# Schematic_monitoring.net
KiCad netlist of a schematic drawn in EasyEDA
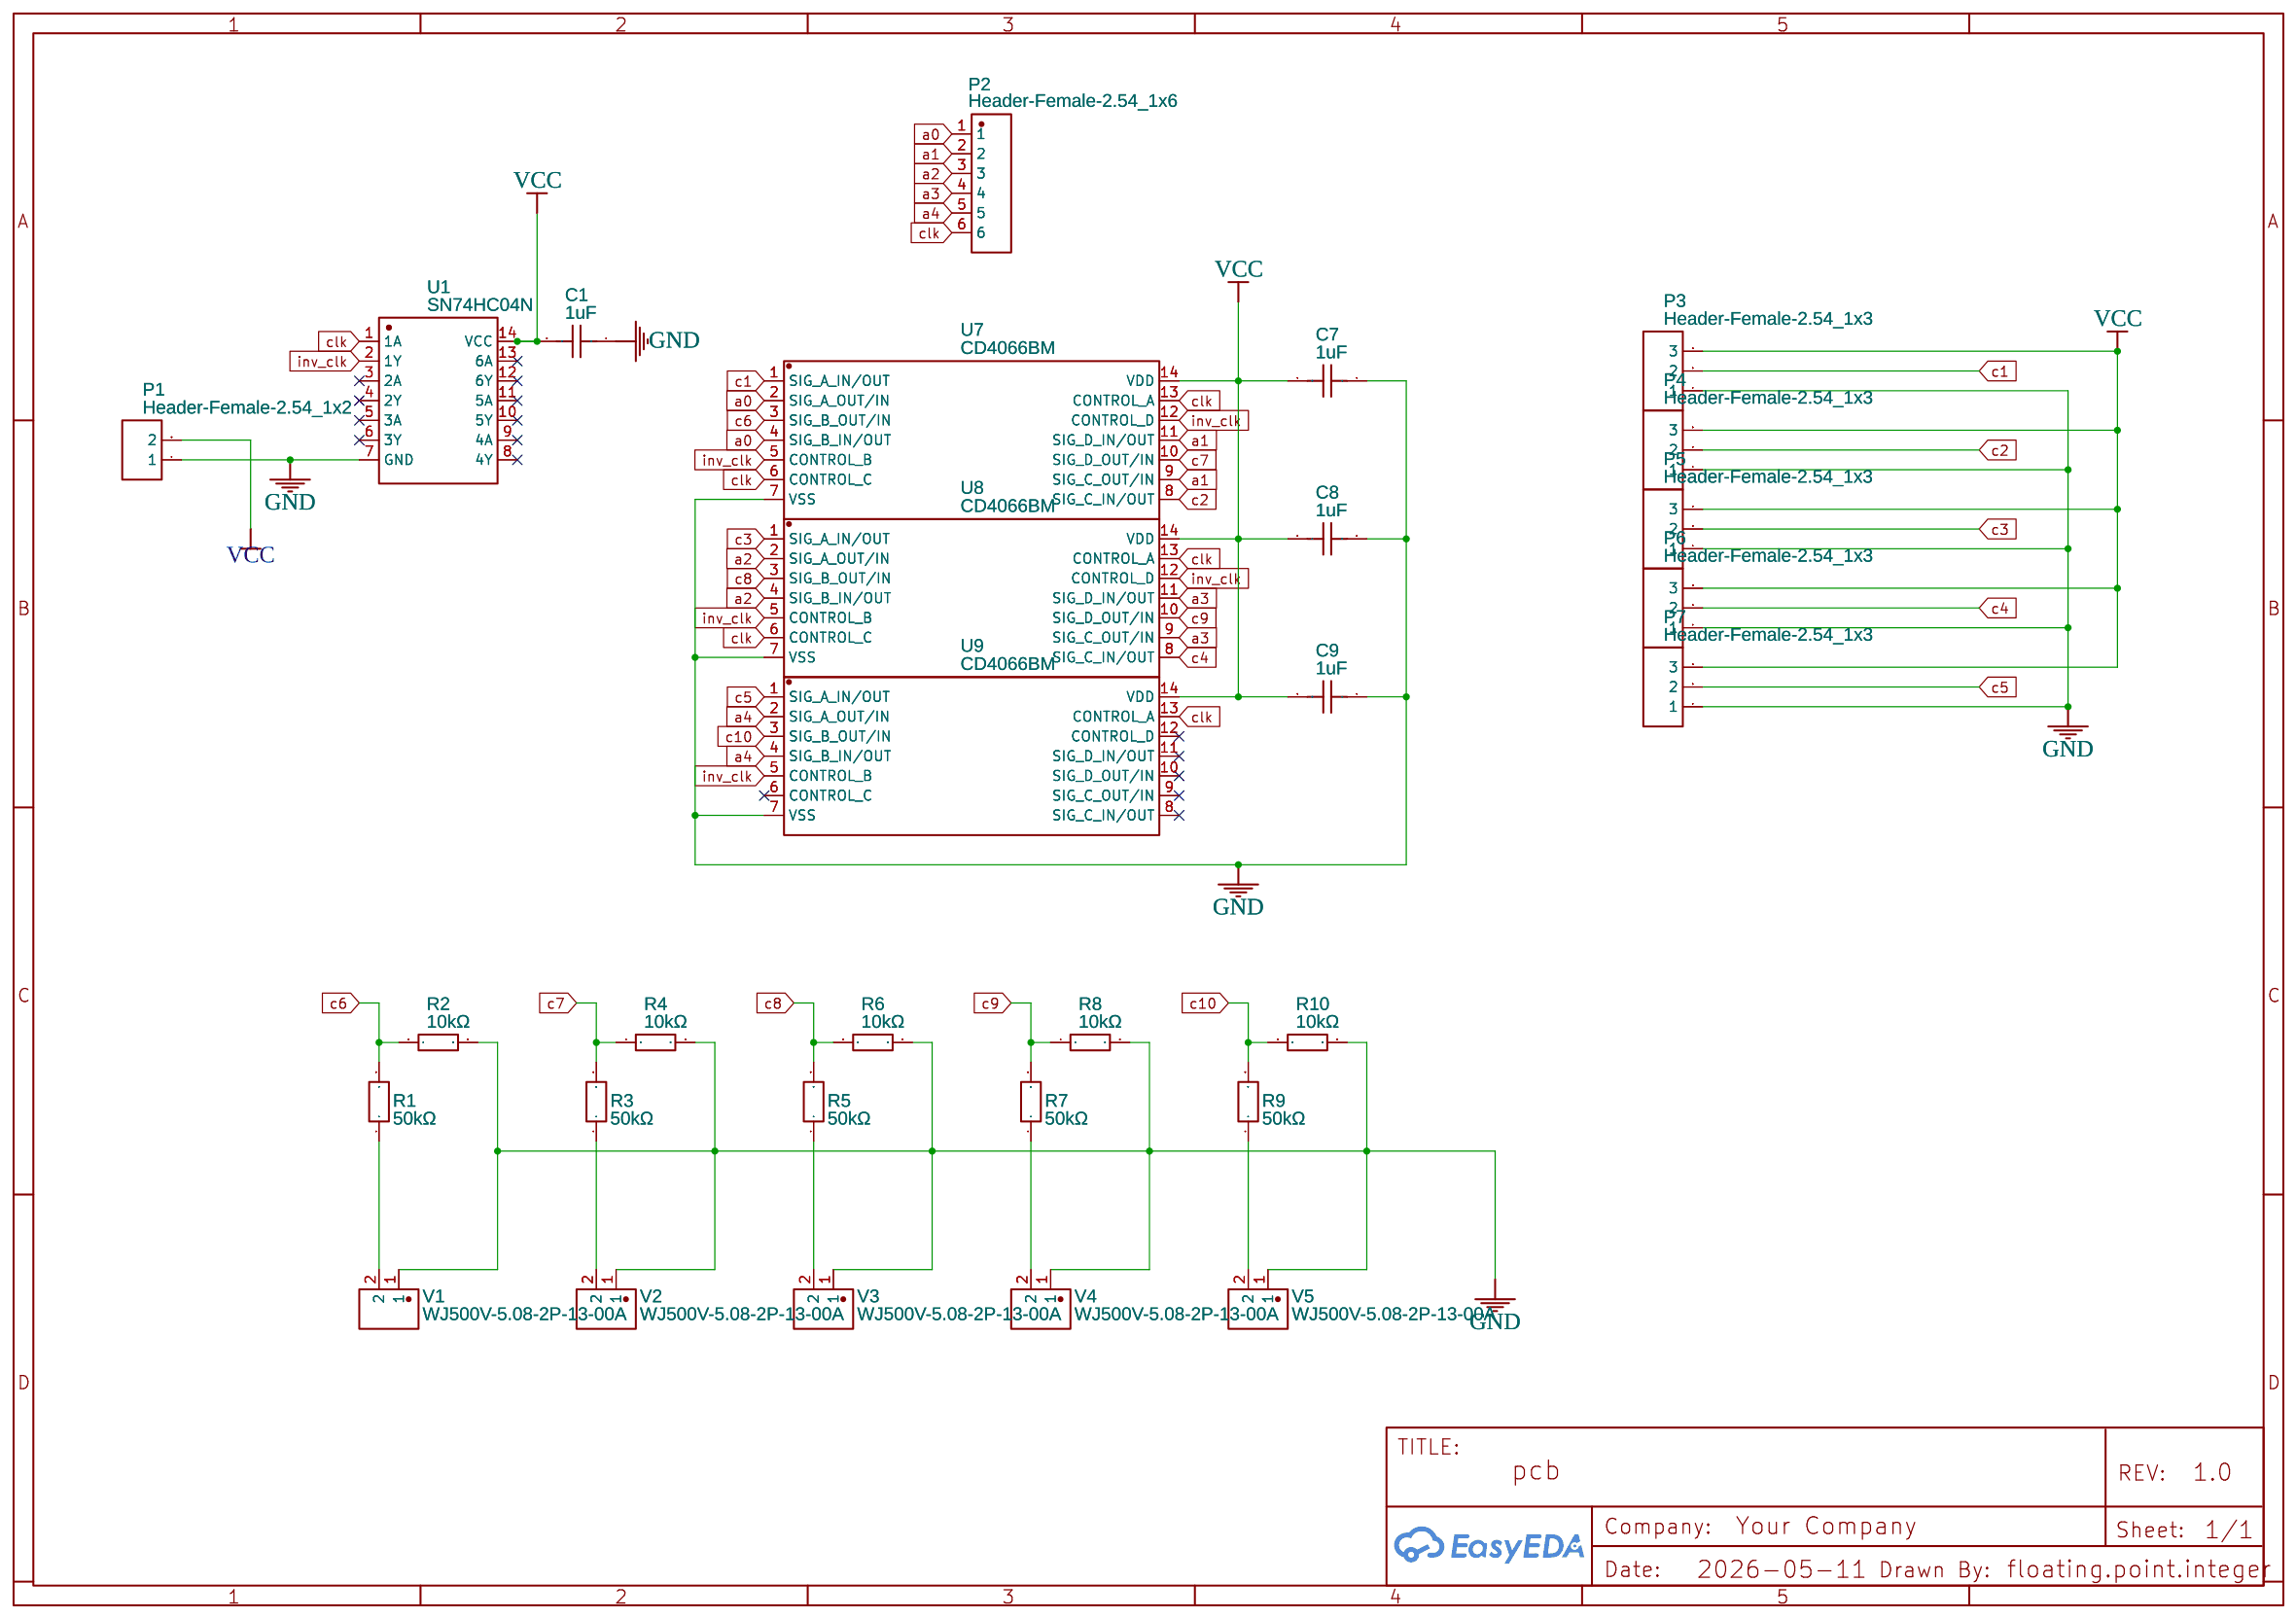
[diagram p0: schematic sheet]

(export (version "E")
  (design (tool "Eeschema 10.0.6"))
  (components
    (comp (ref "C1")
      (value "1uF")
      (fields (field (name "Manufacturer Part") "0603B105K250CT") (field (name "Manufacturer") "Walsin(华新科)"))
      (libsource (lib "") (part "0603B105K250CT"))
    )
    (comp (ref "C7")
      (value "1uF")
      (fields (field (name "Manufacturer Part") "0603B105K250CT") (field (name "Manufacturer") "Walsin(华新科)"))
      (libsource (lib "") (part "0603B105K250CT"))
    )
    (comp (ref "C8")
      (value "1uF")
      (fields (field (name "Manufacturer Part") "0603B105K250CT") (field (name "Manufacturer") "Walsin(华新科)"))
      (libsource (lib "") (part "0603B105K250CT"))
    )
    (comp (ref "C9")
      (value "1uF")
      (fields (field (name "Manufacturer Part") "0603B105K250CT") (field (name "Manufacturer") "Walsin(华新科)"))
      (libsource (lib "") (part "0603B105K250CT"))
    )
    (comp (ref "P1")
      (value "Header-Female-2.54_1x2")
      (fields (field (name "Manufacturer Part") "2.54-1*2P母") (field (name "Manufacturer") "BOOMELE(博穆精密)"))
      (libsource (lib "") (part "Header-Female-2.54_1x2"))
    )
    (comp (ref "P2")
      (value "Header-Female-2.54_1x6")
      (fields (field (name "Manufacturer Part") "2.54-1*6P母") (field (name "Manufacturer") "BOOMELE(博穆精密)"))
      (libsource (lib "") (part "Header-Female-2.54_1x6"))
    )
    (comp (ref "P3")
      (value "Header-Female-2.54_1x3")
      (fields (field (name "Manufacturer Part") "2.54-1*3P母") (field (name "Manufacturer") "BOOMELE(博穆精密)"))
      (libsource (lib "") (part "Header-Female-2.54_1x3"))
    )
    (comp (ref "P4")
      (value "Header-Female-2.54_1x3")
      (fields (field (name "Manufacturer Part") "2.54-1*3P母") (field (name "Manufacturer") "BOOMELE(博穆精密)"))
      (libsource (lib "") (part "Header-Female-2.54_1x3"))
    )
    (comp (ref "P5")
      (value "Header-Female-2.54_1x3")
      (fields (field (name "Manufacturer Part") "2.54-1*3P母") (field (name "Manufacturer") "BOOMELE(博穆精密)"))
      (libsource (lib "") (part "Header-Female-2.54_1x3"))
    )
    (comp (ref "P6")
      (value "Header-Female-2.54_1x3")
      (fields (field (name "Manufacturer Part") "2.54-1*3P母") (field (name "Manufacturer") "BOOMELE(博穆精密)"))
      (libsource (lib "") (part "Header-Female-2.54_1x3"))
    )
    (comp (ref "P7")
      (value "Header-Female-2.54_1x3")
      (fields (field (name "Manufacturer Part") "2.54-1*3P母") (field (name "Manufacturer") "BOOMELE(博穆精密)"))
      (libsource (lib "") (part "Header-Female-2.54_1x3"))
    )
    (comp (ref "R1")
      (value "50kΩ")
      (fields (field (name "Manufacturer Part") "RT0603BRD0750KL") (field (name "Manufacturer") "YAGEO(国巨)"))
      (libsource (lib "") (part "RT0603BRD0750KL"))
    )
    (comp (ref "R2")
      (value "10kΩ")
      (fields (field (name "Manufacturer Part") "RT0603DRD0710KL") (field (name "Manufacturer") "YAGEO(国巨)"))
      (libsource (lib "") (part "RT0603DRD0710KL"))
    )
    (comp (ref "R3")
      (value "50kΩ")
      (fields (field (name "Manufacturer Part") "RT0603BRD0750KL") (field (name "Manufacturer") "YAGEO(国巨)"))
      (libsource (lib "") (part "RT0603BRD0750KL"))
    )
    (comp (ref "R4")
      (value "10kΩ")
      (fields (field (name "Manufacturer Part") "RT0603DRD0710KL") (field (name "Manufacturer") "YAGEO(国巨)"))
      (libsource (lib "") (part "RT0603DRD0710KL"))
    )
    (comp (ref "R5")
      (value "50kΩ")
      (fields (field (name "Manufacturer Part") "RT0603BRD0750KL") (field (name "Manufacturer") "YAGEO(国巨)"))
      (libsource (lib "") (part "RT0603BRD0750KL"))
    )
    (comp (ref "R6")
      (value "10kΩ")
      (fields (field (name "Manufacturer Part") "RT0603DRD0710KL") (field (name "Manufacturer") "YAGEO(国巨)"))
      (libsource (lib "") (part "RT0603DRD0710KL"))
    )
    (comp (ref "R7")
      (value "50kΩ")
      (fields (field (name "Manufacturer Part") "RT0603BRD0750KL") (field (name "Manufacturer") "YAGEO(国巨)"))
      (libsource (lib "") (part "RT0603BRD0750KL"))
    )
    (comp (ref "R8")
      (value "10kΩ")
      (fields (field (name "Manufacturer Part") "RT0603DRD0710KL") (field (name "Manufacturer") "YAGEO(国巨)"))
      (libsource (lib "") (part "RT0603DRD0710KL"))
    )
    (comp (ref "R9")
      (value "50kΩ")
      (fields (field (name "Manufacturer Part") "RT0603BRD0750KL") (field (name "Manufacturer") "YAGEO(国巨)"))
      (libsource (lib "") (part "RT0603BRD0750KL"))
    )
    (comp (ref "R10")
      (value "10kΩ")
      (fields (field (name "Manufacturer Part") "RT0603DRD0710KL") (field (name "Manufacturer") "YAGEO(国巨)"))
      (libsource (lib "") (part "RT0603DRD0710KL"))
    )
    (comp (ref "U1")
      (value "SN74HC04N")
      (fields (field (name "Manufacturer") "TI(德州仪器)"))
      (libsource (lib "") (part "SN74HC04N"))
    )
    (comp (ref "U7")
      (value "CD4066BM")
      (fields (field (name "Manufacturer") "TI(德州仪器)"))
      (libsource (lib "") (part "CD4066BM"))
    )
    (comp (ref "U8")
      (value "CD4066BM")
      (fields (field (name "Manufacturer") "TI(德州仪器)"))
      (libsource (lib "") (part "CD4066BM"))
    )
    (comp (ref "U9")
      (value "CD4066BM")
      (fields (field (name "Manufacturer") "TI(德州仪器)"))
      (libsource (lib "") (part "CD4066BM"))
    )
    (comp (ref "V1")
      (value "WJ500V-5.08-2P-13-00A")
      (fields
        (field (name "Manufacturer Part") "WJ500V-5.08-02P-13-00A")
        (field (name "Manufacturer") "KANGNEX(康奈克斯电气)")
      )
      (libsource (lib "") (part "WJ500V-5.08-2P-13-00A"))
    )
    (comp (ref "V2")
      (value "WJ500V-5.08-2P-13-00A")
      (fields
        (field (name "Manufacturer Part") "WJ500V-5.08-02P-13-00A")
        (field (name "Manufacturer") "KANGNEX(康奈克斯电气)")
      )
      (libsource (lib "") (part "WJ500V-5.08-2P-13-00A"))
    )
    (comp (ref "V3")
      (value "WJ500V-5.08-2P-13-00A")
      (fields
        (field (name "Manufacturer Part") "WJ500V-5.08-02P-13-00A")
        (field (name "Manufacturer") "KANGNEX(康奈克斯电气)")
      )
      (libsource (lib "") (part "WJ500V-5.08-2P-13-00A"))
    )
    (comp (ref "V4")
      (value "WJ500V-5.08-2P-13-00A")
      (fields
        (field (name "Manufacturer Part") "WJ500V-5.08-02P-13-00A")
        (field (name "Manufacturer") "KANGNEX(康奈克斯电气)")
      )
      (libsource (lib "") (part "WJ500V-5.08-2P-13-00A"))
    )
    (comp (ref "V5")
      (value "WJ500V-5.08-2P-13-00A")
      (fields
        (field (name "Manufacturer Part") "WJ500V-5.08-02P-13-00A")
        (field (name "Manufacturer") "KANGNEX(康奈克斯电气)")
      )
      (libsource (lib "") (part "WJ500V-5.08-2P-13-00A"))
    )
  )
  (nets
    (net (code "1") (name "GND") (class "Default")
      (node (ref "C1") (pin "1") (pinfunction "1_1") (pintype "unspecified"))
      (node (ref "C7") (pin "1") (pinfunction "1_1") (pintype "unspecified"))
      (node (ref "C8") (pin "1") (pinfunction "1_1") (pintype "unspecified"))
      (node (ref "C9") (pin "1") (pinfunction "1_1") (pintype "unspecified"))
      (node (ref "P1") (pin "1") (pinfunction "1_1") (pintype "input"))
      (node (ref "P3") (pin "1") (pinfunction "1_1") (pintype "input"))
      (node (ref "P4") (pin "1") (pinfunction "1_1") (pintype "input"))
      (node (ref "P5") (pin "1") (pinfunction "1_1") (pintype "input"))
      (node (ref "P6") (pin "1") (pinfunction "1_1") (pintype "input"))
      (node (ref "P7") (pin "1") (pinfunction "1_1") (pintype "input"))
      (node (ref "R10") (pin "2") (pinfunction "2_2") (pintype "unspecified"))
      (node (ref "R2") (pin "2") (pinfunction "2_2") (pintype "unspecified"))
      (node (ref "R4") (pin "2") (pinfunction "2_2") (pintype "unspecified"))
      (node (ref "R6") (pin "2") (pinfunction "2_2") (pintype "unspecified"))
      (node (ref "R8") (pin "2") (pinfunction "2_2") (pintype "unspecified"))
      (node (ref "U1") (pin "7") (pinfunction "GND_7") (pintype "unspecified"))
      (node (ref "U7") (pin "7") (pinfunction "VSS_7") (pintype "unspecified"))
      (node (ref "U8") (pin "7") (pinfunction "VSS_7") (pintype "unspecified"))
      (node (ref "U9") (pin "7") (pinfunction "VSS_7") (pintype "unspecified"))
      (node (ref "V1") (pin "1") (pinfunction "1_1") (pintype "unspecified"))
      (node (ref "V2") (pin "1") (pinfunction "1_1") (pintype "unspecified"))
      (node (ref "V3") (pin "1") (pinfunction "1_1") (pintype "unspecified"))
      (node (ref "V4") (pin "1") (pinfunction "1_1") (pintype "unspecified"))
      (node (ref "V5") (pin "1") (pinfunction "1_1") (pintype "unspecified"))
    )
    (net (code "2") (name "Net-(R1-Pad1)") (class "Default")
      (node (ref "R1") (pin "1") (pinfunction "1_1") (pintype "unspecified"))
      (node (ref "V1") (pin "2") (pinfunction "2_2") (pintype "unspecified"))
    )
    (net (code "3") (name "Net-(R3-Pad1)") (class "Default")
      (node (ref "R3") (pin "1") (pinfunction "1_1") (pintype "unspecified"))
      (node (ref "V2") (pin "2") (pinfunction "2_2") (pintype "unspecified"))
    )
    (net (code "4") (name "Net-(R5-Pad1)") (class "Default")
      (node (ref "R5") (pin "1") (pinfunction "1_1") (pintype "unspecified"))
      (node (ref "V3") (pin "2") (pinfunction "2_2") (pintype "unspecified"))
    )
    (net (code "5") (name "Net-(R7-Pad1)") (class "Default")
      (node (ref "R7") (pin "1") (pinfunction "1_1") (pintype "unspecified"))
      (node (ref "V4") (pin "2") (pinfunction "2_2") (pintype "unspecified"))
    )
    (net (code "6") (name "Net-(R9-Pad1)") (class "Default")
      (node (ref "R9") (pin "1") (pinfunction "1_1") (pintype "unspecified"))
      (node (ref "V5") (pin "2") (pinfunction "2_2") (pintype "unspecified"))
    )
    (net (code "7") (name "VCC") (class "Default")
      (node (ref "C1") (pin "2") (pinfunction "2_2") (pintype "unspecified"))
      (node (ref "C7") (pin "2") (pinfunction "2_2") (pintype "unspecified"))
      (node (ref "C8") (pin "2") (pinfunction "2_2") (pintype "unspecified"))
      (node (ref "C9") (pin "2") (pinfunction "2_2") (pintype "unspecified"))
      (node (ref "P1") (pin "2") (pinfunction "2_2") (pintype "input"))
      (node (ref "P3") (pin "3") (pinfunction "3_3") (pintype "input"))
      (node (ref "P4") (pin "3") (pinfunction "3_3") (pintype "input"))
      (node (ref "P5") (pin "3") (pinfunction "3_3") (pintype "input"))
      (node (ref "P6") (pin "3") (pinfunction "3_3") (pintype "input"))
      (node (ref "P7") (pin "3") (pinfunction "3_3") (pintype "input"))
      (node (ref "U1") (pin "14") (pinfunction "VCC_14") (pintype "unspecified"))
      (node (ref "U7") (pin "14") (pinfunction "VDD_14") (pintype "unspecified"))
      (node (ref "U8") (pin "14") (pinfunction "VDD_14") (pintype "unspecified"))
      (node (ref "U9") (pin "14") (pinfunction "VDD_14") (pintype "unspecified"))
    )
    (net (code "8") (name "a0") (class "Default")
      (node (ref "P2") (pin "1") (pinfunction "1_1") (pintype "unspecified"))
      (node (ref "U7") (pin "2") (pinfunction "SIG_A_OUT/IN_2") (pintype "unspecified"))
      (node (ref "U7") (pin "4") (pinfunction "SIG_B_IN/OUT_4") (pintype "unspecified"))
    )
    (net (code "9") (name "a1") (class "Default")
      (node (ref "P2") (pin "2") (pinfunction "2_2") (pintype "unspecified"))
      (node (ref "U7") (pin "11") (pinfunction "SIG_D_IN/OUT_11") (pintype "unspecified"))
      (node (ref "U7") (pin "9") (pinfunction "SIG_C_OUT/IN_9") (pintype "unspecified"))
    )
    (net (code "10") (name "a2") (class "Default")
      (node (ref "P2") (pin "3") (pinfunction "3_3") (pintype "unspecified"))
      (node (ref "U8") (pin "2") (pinfunction "SIG_A_OUT/IN_2") (pintype "unspecified"))
      (node (ref "U8") (pin "4") (pinfunction "SIG_B_IN/OUT_4") (pintype "unspecified"))
    )
    (net (code "11") (name "a3") (class "Default")
      (node (ref "P2") (pin "4") (pinfunction "4_4") (pintype "unspecified"))
      (node (ref "U8") (pin "11") (pinfunction "SIG_D_IN/OUT_11") (pintype "unspecified"))
      (node (ref "U8") (pin "9") (pinfunction "SIG_C_OUT/IN_9") (pintype "unspecified"))
    )
    (net (code "12") (name "a4") (class "Default")
      (node (ref "P2") (pin "5") (pinfunction "5_5") (pintype "unspecified"))
      (node (ref "U9") (pin "2") (pinfunction "SIG_A_OUT/IN_2") (pintype "unspecified"))
      (node (ref "U9") (pin "4") (pinfunction "SIG_B_IN/OUT_4") (pintype "unspecified"))
    )
    (net (code "13") (name "c1") (class "Default")
      (node (ref "P3") (pin "2") (pinfunction "2_2") (pintype "input"))
      (node (ref "U7") (pin "1") (pinfunction "SIG_A_IN/OUT_1") (pintype "unspecified"))
    )
    (net (code "14") (name "c2") (class "Default")
      (node (ref "P4") (pin "2") (pinfunction "2_2") (pintype "input"))
      (node (ref "U7") (pin "8") (pinfunction "SIG_C_IN/OUT_8") (pintype "unspecified"))
    )
    (net (code "15") (name "c3") (class "Default")
      (node (ref "P5") (pin "2") (pinfunction "2_2") (pintype "input"))
      (node (ref "U8") (pin "1") (pinfunction "SIG_A_IN/OUT_1") (pintype "unspecified"))
    )
    (net (code "16") (name "c4") (class "Default")
      (node (ref "P6") (pin "2") (pinfunction "2_2") (pintype "input"))
      (node (ref "U8") (pin "8") (pinfunction "SIG_C_IN/OUT_8") (pintype "unspecified"))
    )
    (net (code "17") (name "c5") (class "Default")
      (node (ref "P7") (pin "2") (pinfunction "2_2") (pintype "input"))
      (node (ref "U9") (pin "1") (pinfunction "SIG_A_IN/OUT_1") (pintype "unspecified"))
    )
    (net (code "18") (name "c6") (class "Default")
      (node (ref "R1") (pin "2") (pinfunction "2_2") (pintype "unspecified"))
      (node (ref "R2") (pin "1") (pinfunction "1_1") (pintype "unspecified"))
      (node (ref "U7") (pin "3") (pinfunction "SIG_B_OUT/IN_3") (pintype "unspecified"))
    )
    (net (code "19") (name "c7") (class "Default")
      (node (ref "R3") (pin "2") (pinfunction "2_2") (pintype "unspecified"))
      (node (ref "R4") (pin "1") (pinfunction "1_1") (pintype "unspecified"))
      (node (ref "U7") (pin "10") (pinfunction "SIG_D_OUT/IN_10") (pintype "unspecified"))
    )
    (net (code "20") (name "c8") (class "Default")
      (node (ref "R5") (pin "2") (pinfunction "2_2") (pintype "unspecified"))
      (node (ref "R6") (pin "1") (pinfunction "1_1") (pintype "unspecified"))
      (node (ref "U8") (pin "3") (pinfunction "SIG_B_OUT/IN_3") (pintype "unspecified"))
    )
    (net (code "21") (name "c9") (class "Default")
      (node (ref "R7") (pin "2") (pinfunction "2_2") (pintype "unspecified"))
      (node (ref "R8") (pin "1") (pinfunction "1_1") (pintype "unspecified"))
      (node (ref "U8") (pin "10") (pinfunction "SIG_D_OUT/IN_10") (pintype "unspecified"))
    )
    (net (code "22") (name "c10") (class "Default")
      (node (ref "R10") (pin "1") (pinfunction "1_1") (pintype "unspecified"))
      (node (ref "R9") (pin "2") (pinfunction "2_2") (pintype "unspecified"))
      (node (ref "U9") (pin "3") (pinfunction "SIG_B_OUT/IN_3") (pintype "unspecified"))
    )
    (net (code "23") (name "clk") (class "Default")
      (node (ref "P2") (pin "6") (pinfunction "6_6") (pintype "unspecified"))
      (node (ref "U1") (pin "1") (pinfunction "1A_1") (pintype "unspecified"))
      (node (ref "U7") (pin "13") (pinfunction "CONTROL_A_13") (pintype "unspecified"))
      (node (ref "U7") (pin "6") (pinfunction "CONTROL_C_6") (pintype "unspecified"))
      (node (ref "U8") (pin "13") (pinfunction "CONTROL_A_13") (pintype "unspecified"))
      (node (ref "U8") (pin "6") (pinfunction "CONTROL_C_6") (pintype "unspecified"))
      (node (ref "U9") (pin "13") (pinfunction "CONTROL_A_13") (pintype "unspecified"))
    )
    (net (code "24") (name "inv_clk") (class "Default")
      (node (ref "U1") (pin "2") (pinfunction "1Y_2") (pintype "unspecified"))
      (node (ref "U7") (pin "12") (pinfunction "CONTROL_D_12") (pintype "unspecified"))
      (node (ref "U7") (pin "5") (pinfunction "CONTROL_B_5") (pintype "unspecified"))
      (node (ref "U8") (pin "12") (pinfunction "CONTROL_D_12") (pintype "unspecified"))
      (node (ref "U8") (pin "5") (pinfunction "CONTROL_B_5") (pintype "unspecified"))
      (node (ref "U9") (pin "5") (pinfunction "CONTROL_B_5") (pintype "unspecified"))
    )
    (net (code "25") (name "unconnected-(U1-2A-Pad3)") (class "Default")
      (node (ref "U1") (pin "3") (pinfunction "2A_3") (pintype "unspecified+no_connect"))
    )
    (net (code "26") (name "unconnected-(U1-2Y-Pad4)") (class "Default")
      (node (ref "U1") (pin "4") (pinfunction "2Y_4") (pintype "unspecified+no_connect"))
    )
    (net (code "27") (name "unconnected-(U1-3A-Pad5)") (class "Default")
      (node (ref "U1") (pin "5") (pinfunction "3A_5") (pintype "unspecified+no_connect"))
    )
    (net (code "28") (name "unconnected-(U1-3Y-Pad6)") (class "Default")
      (node (ref "U1") (pin "6") (pinfunction "3Y_6") (pintype "unspecified+no_connect"))
    )
    (net (code "29") (name "unconnected-(U1-4A-Pad9)") (class "Default")
      (node (ref "U1") (pin "9") (pinfunction "4A_9") (pintype "unspecified+no_connect"))
    )
    (net (code "30") (name "unconnected-(U1-4Y-Pad8)") (class "Default")
      (node (ref "U1") (pin "8") (pinfunction "4Y_8") (pintype "unspecified+no_connect"))
    )
    (net (code "31") (name "unconnected-(U1-5A-Pad11)") (class "Default")
      (node (ref "U1") (pin "11") (pinfunction "5A_11") (pintype "unspecified+no_connect"))
    )
    (net (code "32") (name "unconnected-(U1-5Y-Pad10)") (class "Default")
      (node (ref "U1") (pin "10") (pinfunction "5Y_10") (pintype "unspecified+no_connect"))
    )
    (net (code "33") (name "unconnected-(U1-6A-Pad13)") (class "Default")
      (node (ref "U1") (pin "13") (pinfunction "6A_13") (pintype "unspecified+no_connect"))
    )
    (net (code "34") (name "unconnected-(U1-6Y-Pad12)") (class "Default")
      (node (ref "U1") (pin "12") (pinfunction "6Y_12") (pintype "unspecified+no_connect"))
    )
    (net (code "35") (name "unconnected-(U9-CONTROL_C-Pad6)") (class "Default")
      (node (ref "U9") (pin "6") (pinfunction "CONTROL_C_6") (pintype "unspecified+no_connect"))
    )
    (net (code "36") (name "unconnected-(U9-CONTROL_D-Pad12)") (class "Default")
      (node (ref "U9") (pin "12") (pinfunction "CONTROL_D_12") (pintype "unspecified+no_connect"))
    )
    (net (code "37") (name "unconnected-(U9-SIG_C_IN{slash}OUT-Pad8)") (class "Default")
      (node (ref "U9") (pin "8") (pinfunction "SIG_C_IN/OUT_8") (pintype "unspecified+no_connect"))
    )
    (net (code "38") (name "unconnected-(U9-SIG_C_OUT{slash}IN-Pad9)") (class "Default")
      (node (ref "U9") (pin "9") (pinfunction "SIG_C_OUT/IN_9") (pintype "unspecified+no_connect"))
    )
    (net (code "39") (name "unconnected-(U9-SIG_D_IN{slash}OUT-Pad11)") (class "Default")
      (node (ref "U9") (pin "11") (pinfunction "SIG_D_IN/OUT_11") (pintype "unspecified+no_connect"))
    )
    (net (code "40") (name "unconnected-(U9-SIG_D_OUT{slash}IN-Pad10)") (class "Default")
      (node (ref "U9") (pin "10") (pinfunction "SIG_D_OUT/IN_10") (pintype "unspecified+no_connect"))
    )
  )
)
